# self-balancing-robot.net
KiCad netlist of a schematic drawn in EasyEDA Pro
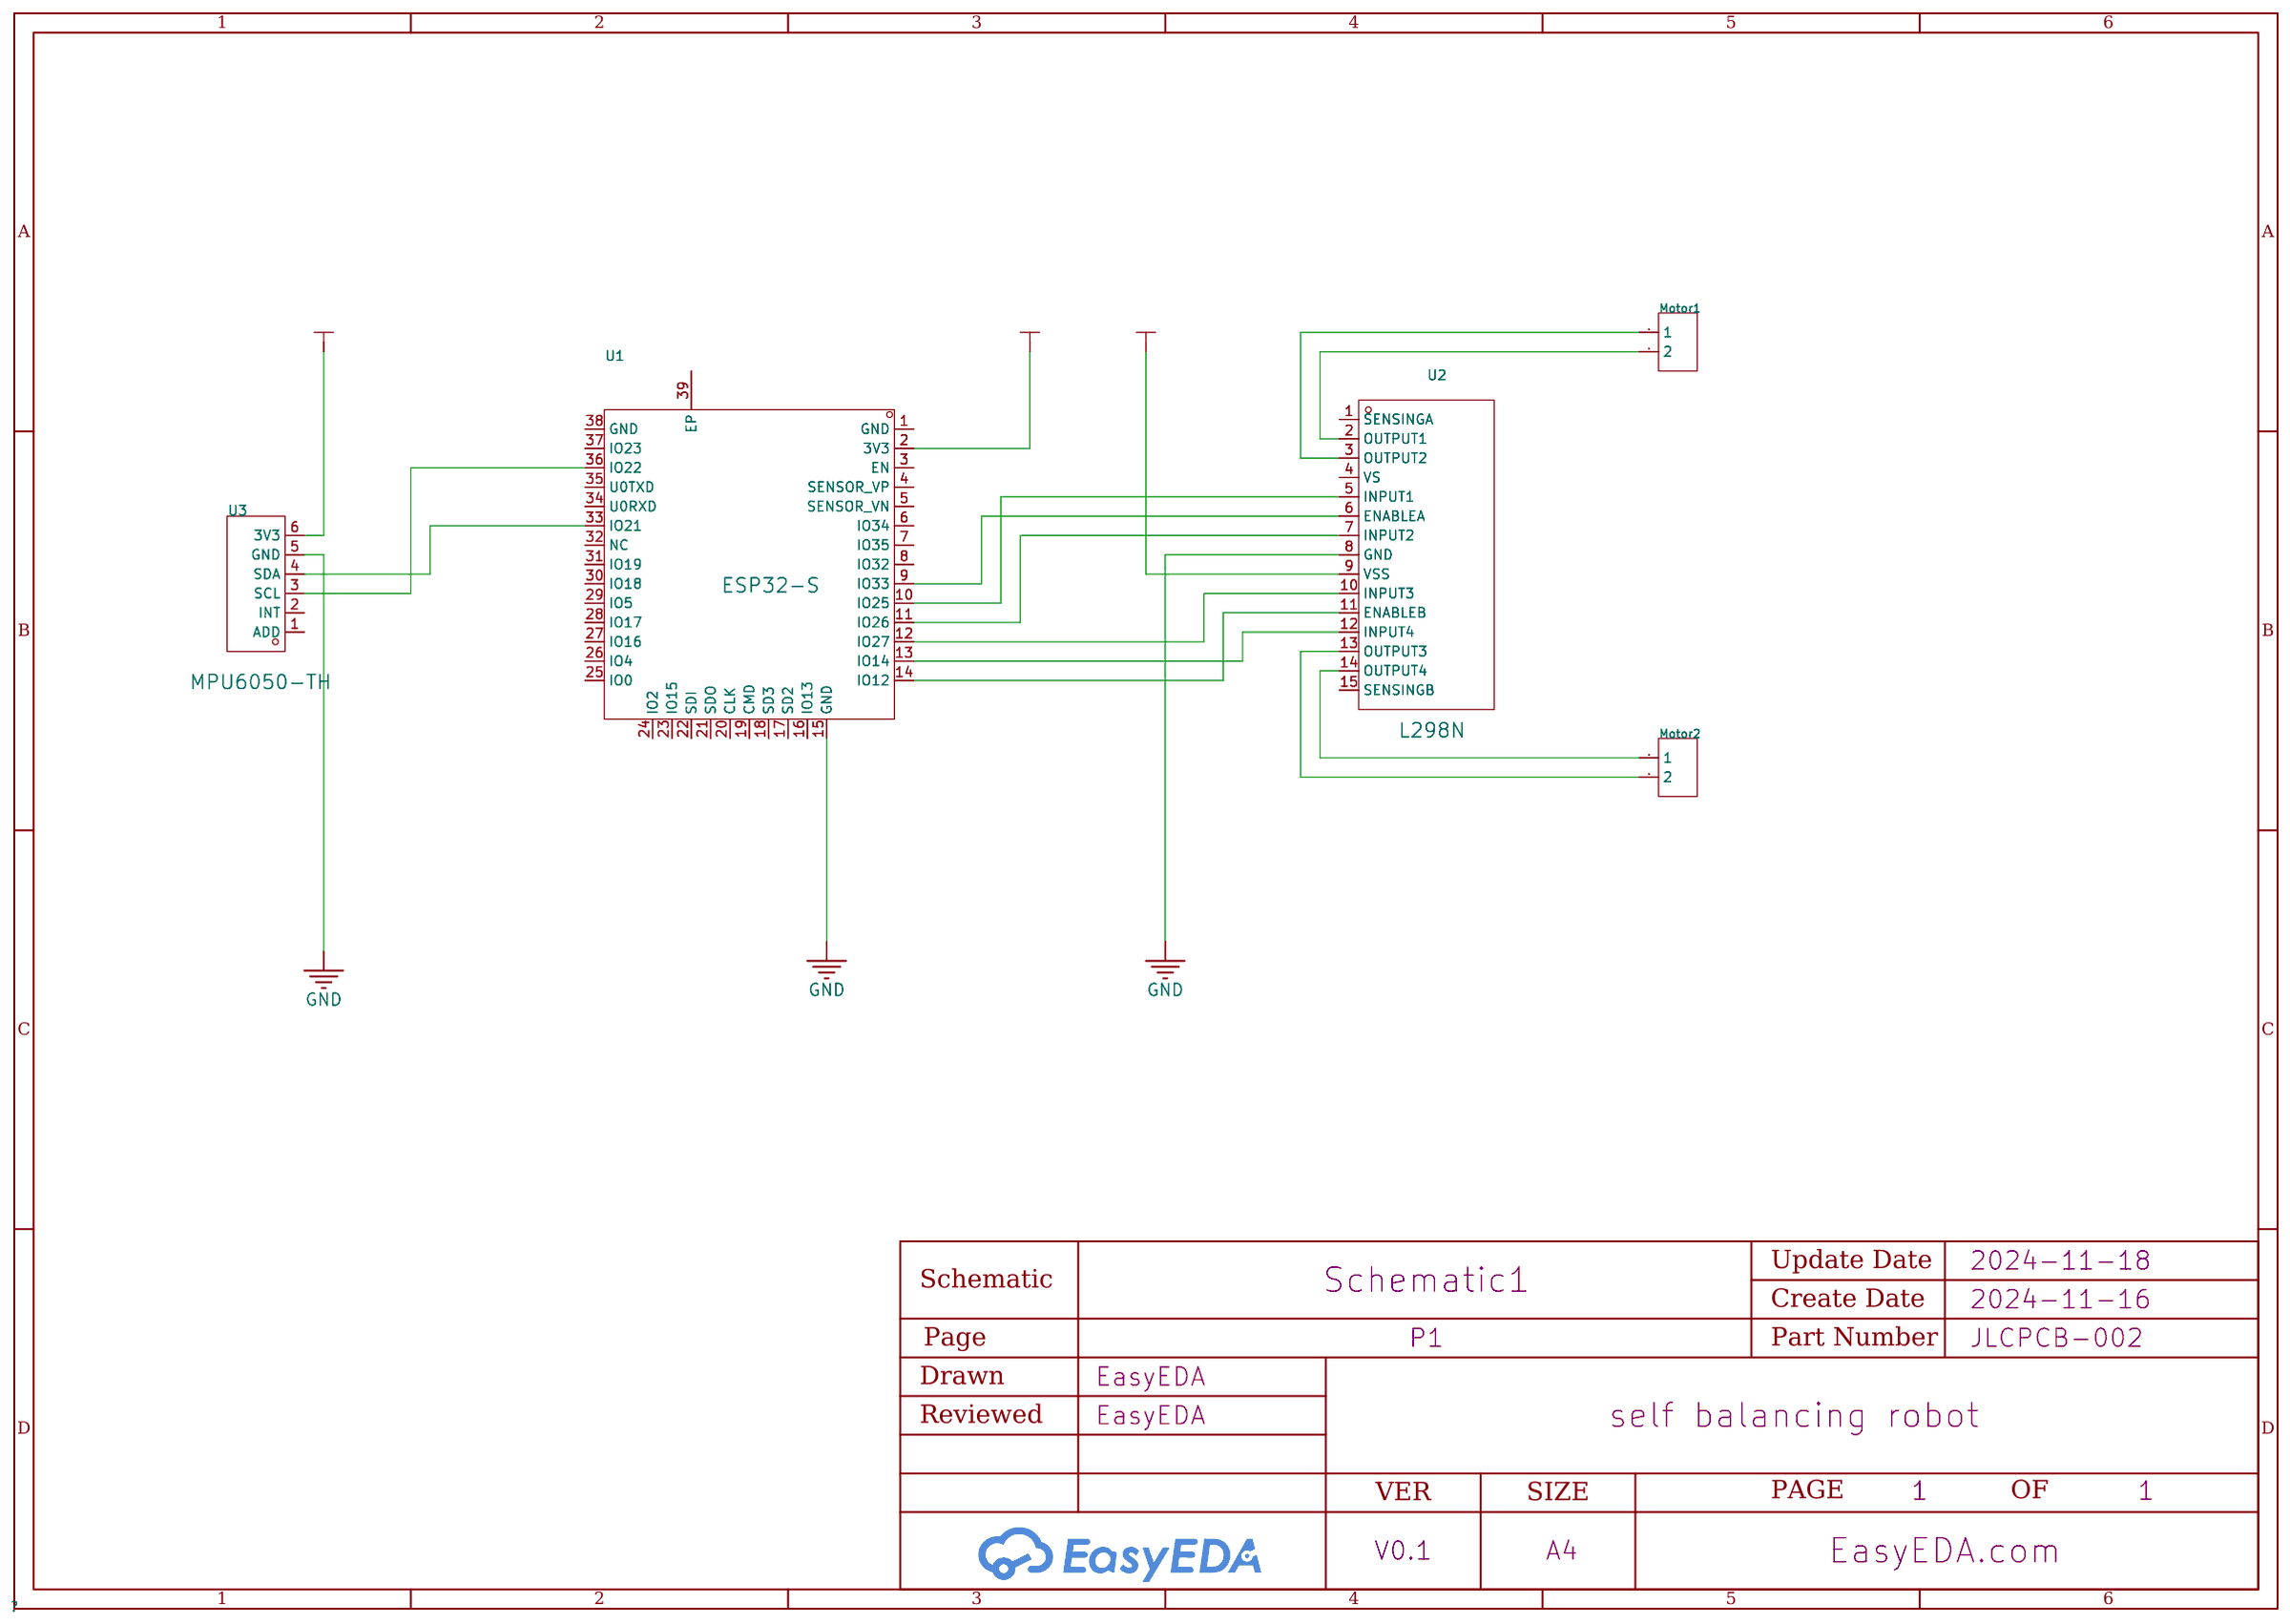
[diagram p0: schematic sheet]

(export (version "E")
  (design (tool "Eeschema 10.0.6"))
  (components
    (comp (ref "Motor1")
      (value "~")
      (footprint "easyedapro:HDR-TH_2P-P2.54-V-F")
      (libsource (lib "easyedapro") (part "Header-Female-2.54_1x2"))
    )
    (comp (ref "Motor2")
      (value "~")
      (footprint "easyedapro:HDR-TH_2P-P2.54-V-F")
      (libsource (lib "easyedapro") (part "Header-Female-2.54_1x2"))
    )
    (comp (ref "U1")
      (value "2.4GHz")
      (footprint "easyedapro:WIRELM-SMD_ESP32-S")
      (fields (field (name "Manufacturer Part") "ESP32-S") (field (name "Manufacturer") "Ai-Thinker(安信可)"))
      (libsource (lib "easyedapro") (part "ESP32-S"))
    )
    (comp (ref "U2")
      (value "L298N")
      (footprint "easyedapro:MULTIWATT-15_L19.6-W5.0-P1.27-L")
      (libsource (lib "easyedapro") (part "L298N_C504386"))
    )
    (comp (ref "U3")
      (value "MPU6050-TH")
      (footprint "easyedapro:COMM-TH_MPU6050-TH")
      (libsource (lib "easyedapro") (part "MPU6050-TH"))
    )
  )
  (nets
    (net (code "1") (name "3.3V") (class "Default")
      (node (ref "U1") (pin "2") (pinfunction "3V3_2") (pintype "input"))
      (node (ref "U3") (pin "6") (pinfunction "3V3_6") (pintype "unspecified"))
    )
    (net (code "2") (name "7.4V") (class "Default")
      (node (ref "U2") (pin "9") (pinfunction "VSS_9") (pintype "unspecified"))
    )
    (net (code "3") (name "GND") (class "Default")
      (node (ref "U1") (pin "15") (pinfunction "GND_15") (pintype "input"))
      (node (ref "U2") (pin "8") (pinfunction "GND_8") (pintype "unspecified"))
      (node (ref "U3") (pin "5") (pinfunction "GND_5") (pintype "unspecified"))
    )
    (net (code "4") (name "Net-(U1-IO12)") (class "Default")
      (node (ref "U1") (pin "14") (pinfunction "IO12_14") (pintype "input"))
      (node (ref "U2") (pin "11") (pinfunction "ENABLEB_11") (pintype "unspecified"))
    )
    (net (code "5") (name "Net-(U1-IO14)") (class "Default")
      (node (ref "U1") (pin "13") (pinfunction "IO14_13") (pintype "input"))
      (node (ref "U2") (pin "12") (pinfunction "INPUT4_12") (pintype "unspecified"))
    )
    (net (code "6") (name "Net-(U1-IO21)") (class "Default")
      (node (ref "U1") (pin "33") (pinfunction "IO21_33") (pintype "input"))
      (node (ref "U3") (pin "4") (pinfunction "SDA_4") (pintype "unspecified"))
    )
    (net (code "7") (name "Net-(U1-IO22)") (class "Default")
      (node (ref "U1") (pin "36") (pinfunction "IO22_36") (pintype "input"))
      (node (ref "U3") (pin "3") (pinfunction "SCL_3") (pintype "unspecified"))
    )
    (net (code "8") (name "Net-(U1-IO25)") (class "Default")
      (node (ref "U1") (pin "10") (pinfunction "IO25_10") (pintype "input"))
      (node (ref "U2") (pin "5") (pinfunction "INPUT1_5") (pintype "unspecified"))
    )
    (net (code "9") (name "Net-(U1-IO26)") (class "Default")
      (node (ref "U1") (pin "11") (pinfunction "IO26_11") (pintype "input"))
      (node (ref "U2") (pin "7") (pinfunction "INPUT2_7") (pintype "unspecified"))
    )
    (net (code "10") (name "Net-(U1-IO27)") (class "Default")
      (node (ref "U1") (pin "12") (pinfunction "IO27_12") (pintype "input"))
      (node (ref "U2") (pin "10") (pinfunction "INPUT3_10") (pintype "unspecified"))
    )
    (net (code "11") (name "Net-(U1-IO33)") (class "Default")
      (node (ref "U1") (pin "9") (pinfunction "IO33_9") (pintype "input"))
      (node (ref "U2") (pin "6") (pinfunction "ENABLEA_6") (pintype "unspecified"))
    )
    (net (code "12") (name "Net-(U2-OUTPUT1)") (class "Default")
      (node (ref "Motor1") (pin "2") (pinfunction "2_2") (pintype "input"))
      (node (ref "U2") (pin "2") (pinfunction "OUTPUT1_2") (pintype "unspecified"))
    )
    (net (code "13") (name "Net-(U2-OUTPUT2)") (class "Default")
      (node (ref "Motor1") (pin "1") (pinfunction "1_1") (pintype "input"))
      (node (ref "U2") (pin "3") (pinfunction "OUTPUT2_3") (pintype "unspecified"))
    )
    (net (code "14") (name "Net-(U2-OUTPUT3)") (class "Default")
      (node (ref "Motor2") (pin "2") (pinfunction "2_2") (pintype "input"))
      (node (ref "U2") (pin "13") (pinfunction "OUTPUT3_13") (pintype "unspecified"))
    )
    (net (code "15") (name "Net-(U2-OUTPUT4)") (class "Default")
      (node (ref "Motor2") (pin "1") (pinfunction "1_1") (pintype "input"))
      (node (ref "U2") (pin "14") (pinfunction "OUTPUT4_14") (pintype "unspecified"))
    )
    (net (code "16") (name "unconnected-(U1-CLK-Pad20)") (class "Default")
      (node (ref "U1") (pin "20") (pinfunction "CLK_20") (pintype "input"))
    )
    (net (code "17") (name "unconnected-(U1-CMD-Pad19)") (class "Default")
      (node (ref "U1") (pin "19") (pinfunction "CMD_19") (pintype "input"))
    )
    (net (code "18") (name "unconnected-(U1-EN-Pad3)") (class "Default")
      (node (ref "U1") (pin "3") (pinfunction "EN_3") (pintype "input"))
    )
    (net (code "19") (name "unconnected-(U1-EP-Pad39)") (class "Default")
      (node (ref "U1") (pin "39") (pinfunction "EP_39") (pintype "input"))
    )
    (net (code "20") (name "unconnected-(U1-GND-Pad1)") (class "Default")
      (node (ref "U1") (pin "1") (pinfunction "GND_1") (pintype "input"))
    )
    (net (code "21") (name "unconnected-(U1-GND-Pad38)") (class "Default")
      (node (ref "U1") (pin "38") (pinfunction "GND_38") (pintype "input"))
    )
    (net (code "22") (name "unconnected-(U1-IO0-Pad25)") (class "Default")
      (node (ref "U1") (pin "25") (pinfunction "IO0_25") (pintype "input"))
    )
    (net (code "23") (name "unconnected-(U1-IO2-Pad24)") (class "Default")
      (node (ref "U1") (pin "24") (pinfunction "IO2_24") (pintype "input"))
    )
    (net (code "24") (name "unconnected-(U1-IO4-Pad26)") (class "Default")
      (node (ref "U1") (pin "26") (pinfunction "IO4_26") (pintype "input"))
    )
    (net (code "25") (name "unconnected-(U1-IO5-Pad29)") (class "Default")
      (node (ref "U1") (pin "29") (pinfunction "IO5_29") (pintype "input"))
    )
    (net (code "26") (name "unconnected-(U1-IO13-Pad16)") (class "Default")
      (node (ref "U1") (pin "16") (pinfunction "IO13_16") (pintype "input"))
    )
    (net (code "27") (name "unconnected-(U1-IO15-Pad23)") (class "Default")
      (node (ref "U1") (pin "23") (pinfunction "IO15_23") (pintype "input"))
    )
    (net (code "28") (name "unconnected-(U1-IO16-Pad27)") (class "Default")
      (node (ref "U1") (pin "27") (pinfunction "IO16_27") (pintype "input"))
    )
    (net (code "29") (name "unconnected-(U1-IO17-Pad28)") (class "Default")
      (node (ref "U1") (pin "28") (pinfunction "IO17_28") (pintype "input"))
    )
    (net (code "30") (name "unconnected-(U1-IO18-Pad30)") (class "Default")
      (node (ref "U1") (pin "30") (pinfunction "IO18_30") (pintype "input"))
    )
    (net (code "31") (name "unconnected-(U1-IO19-Pad31)") (class "Default")
      (node (ref "U1") (pin "31") (pinfunction "IO19_31") (pintype "input"))
    )
    (net (code "32") (name "unconnected-(U1-IO23-Pad37)") (class "Default")
      (node (ref "U1") (pin "37") (pinfunction "IO23_37") (pintype "input"))
    )
    (net (code "33") (name "unconnected-(U1-IO32-Pad8)") (class "Default")
      (node (ref "U1") (pin "8") (pinfunction "IO32_8") (pintype "input"))
    )
    (net (code "34") (name "unconnected-(U1-IO34-Pad6)") (class "Default")
      (node (ref "U1") (pin "6") (pinfunction "IO34_6") (pintype "input"))
    )
    (net (code "35") (name "unconnected-(U1-IO35-Pad7)") (class "Default")
      (node (ref "U1") (pin "7") (pinfunction "IO35_7") (pintype "input"))
    )
    (net (code "36") (name "unconnected-(U1-NC-Pad32)") (class "Default")
      (node (ref "U1") (pin "32") (pinfunction "NC_32") (pintype "input"))
    )
    (net (code "37") (name "unconnected-(U1-SD2-Pad17)") (class "Default")
      (node (ref "U1") (pin "17") (pinfunction "SD2_17") (pintype "input"))
    )
    (net (code "38") (name "unconnected-(U1-SD3-Pad18)") (class "Default")
      (node (ref "U1") (pin "18") (pinfunction "SD3_18") (pintype "input"))
    )
    (net (code "39") (name "unconnected-(U1-SDI-Pad22)") (class "Default")
      (node (ref "U1") (pin "22") (pinfunction "SDI_22") (pintype "input"))
    )
    (net (code "40") (name "unconnected-(U1-SDO-Pad21)") (class "Default")
      (node (ref "U1") (pin "21") (pinfunction "SDO_21") (pintype "input"))
    )
    (net (code "41") (name "unconnected-(U1-SENSOR_VN-Pad5)") (class "Default")
      (node (ref "U1") (pin "5") (pinfunction "SENSOR_VN_5") (pintype "input"))
    )
    (net (code "42") (name "unconnected-(U1-SENSOR_VP-Pad4)") (class "Default")
      (node (ref "U1") (pin "4") (pinfunction "SENSOR_VP_4") (pintype "input"))
    )
    (net (code "43") (name "unconnected-(U1-U0RXD-Pad34)") (class "Default")
      (node (ref "U1") (pin "34") (pinfunction "U0RXD_34") (pintype "input"))
    )
    (net (code "44") (name "unconnected-(U1-U0TXD-Pad35)") (class "Default")
      (node (ref "U1") (pin "35") (pinfunction "U0TXD_35") (pintype "input"))
    )
    (net (code "45") (name "unconnected-(U2-SENSINGA-Pad1)") (class "Default")
      (node (ref "U2") (pin "1") (pinfunction "SENSINGA_1") (pintype "unspecified"))
    )
    (net (code "46") (name "unconnected-(U2-SENSINGB-Pad15)") (class "Default")
      (node (ref "U2") (pin "15") (pinfunction "SENSINGB_15") (pintype "unspecified"))
    )
    (net (code "47") (name "unconnected-(U2-VS-Pad4)") (class "Default")
      (node (ref "U2") (pin "4") (pinfunction "VS_4") (pintype "unspecified"))
    )
    (net (code "48") (name "unconnected-(U3-ADD-Pad1)") (class "Default")
      (node (ref "U3") (pin "1") (pinfunction "ADD_1") (pintype "unspecified"))
    )
    (net (code "49") (name "unconnected-(U3-INT-Pad2)") (class "Default")
      (node (ref "U3") (pin "2") (pinfunction "INT_2") (pintype "unspecified"))
    )
  )
)
